# DC_buck_converter_3_3V_OP.net
KiCad netlist of a schematic drawn in Altium Designer
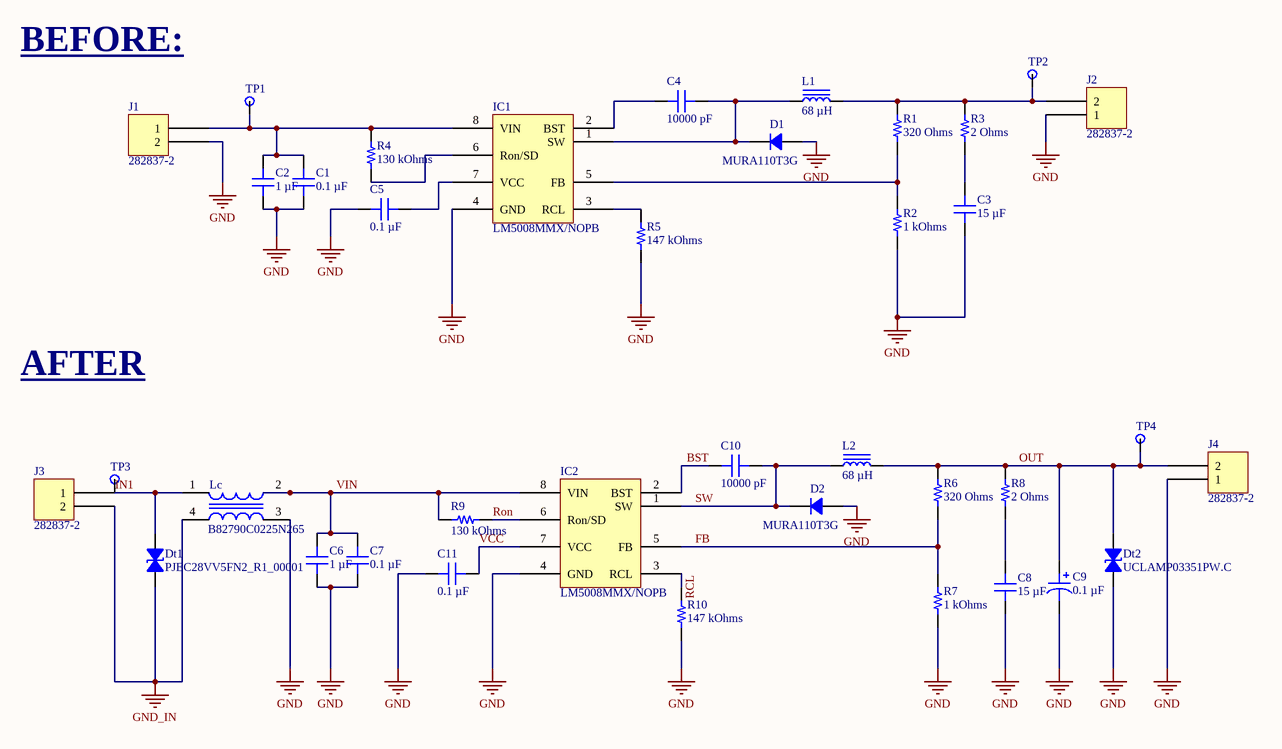
[diagram p0: DC_buck_converter_3.3V_OP..SchDoc]

(export (version "E")
  (design (tool "Eeschema 10.0.6"))
  (components
    (comp (ref "C1")
      (value "0.1 µF")
      (footprint "CAP 0603_1608")
      (description "CAP CER 0.1UF 50V X7R 0603")
      (fields (field (name "PART NUMBER") "C0603C104K5RAC7411") (field (name "MANUFACTURER") "KEMET"))
      (libsource (lib "Celestial Altium Library - altium_library") (part "Capacitor"))
    )
    (comp (ref "C2")
      (value "1 µF")
      (footprint "CAP 0603_1608")
      (description "CAP CER 1UF 50V X5R 0603")
      (fields (field (name "PART NUMBER") "UMK107ABJ105MAHT") (field (name "MANUFACTURER") "Taiyo Yuden"))
      (libsource (lib "Celestial Altium Library - altium_library") (part "Capacitor"))
    )
    (comp (ref "C3")
      (value "15 µF")
      (footprint "CAP 0603_1608")
      (description "CAP CER 15UF 6.3V X5R 0603")
      (fields
        (field (name "PART NUMBER") "C1608X5R0J156M080AC")
        (field (name "MANUFACTURER") "TDK Corporation")
      )
      (libsource (lib "Celestial Altium Library - altium_library") (part "Capacitor"))
    )
    (comp (ref "C4")
      (value "10000 pF")
      (footprint "CAP 0603_1608")
      (description "CAP CER 10000PF 100V X7R 0603")
      (fields (field (name "PART NUMBER") "AC0603KRX7R0BB103") (field (name "MANUFACTURER") "Yageo"))
      (libsource (lib "Celestial Altium Library - altium_library") (part "Capacitor"))
    )
    (comp (ref "C5")
      (value "0.1 µF")
      (footprint "CAP 0603_1608")
      (description "CAP CER 0.1UF 50V X7R 0603")
      (fields (field (name "PART NUMBER") "C0603C104K5RAC7411") (field (name "MANUFACTURER") "KEMET"))
      (libsource (lib "Celestial Altium Library - altium_library") (part "Capacitor"))
    )
    (comp (ref "C6")
      (value "1 µF")
      (footprint "CAP 0603_1608")
      (description "CAP CER 1UF 50V X5R 0603")
      (fields (field (name "PART NUMBER") "UMK107ABJ105MAHT") (field (name "MANUFACTURER") "Taiyo Yuden"))
      (libsource (lib "Celestial Altium Library - altium_library") (part "Capacitor"))
    )
    (comp (ref "C7")
      (value "0.1 µF")
      (footprint "CAP 0603_1608")
      (description "CAP CER 0.1UF 50V X7R 0603")
      (fields (field (name "PART NUMBER") "C0603C104K5RAC7411") (field (name "MANUFACTURER") "KEMET"))
      (libsource (lib "Celestial Altium Library - altium_library") (part "Capacitor"))
    )
    (comp (ref "C8")
      (value "15 µF")
      (footprint "CAP 0603_1608")
      (description "CAP CER 15UF 6.3V X5R 0603")
      (fields
        (field (name "PART NUMBER") "C1608X5R0J156M080AC")
        (field (name "MANUFACTURER") "TDK Corporation")
      )
      (libsource (lib "Celestial Altium Library - altium_library") (part "Capacitor"))
    )
    (comp (ref "C9")
      (value "0.1 µF")
      (footprint "CAP POL 1206_3216")
      (description "CAP TANT 0.1UF 10% 35V 1206")
      (fields (field (name "PART NUMBER") "T494A104K035AT") (field (name "MANUFACTURER") "KEMET"))
      (libsource (lib "Celestial Altium Library - altium_library") (part "Polarised Capacitor"))
    )
    (comp (ref "C10")
      (value "10000 pF")
      (footprint "CAP 0603_1608")
      (description "CAP CER 10000PF 100V X7R 0603")
      (fields (field (name "PART NUMBER") "AC0603KRX7R0BB103") (field (name "MANUFACTURER") "Yageo"))
      (libsource (lib "Celestial Altium Library - altium_library") (part "Capacitor"))
    )
    (comp (ref "C11")
      (value "0.1 µF")
      (footprint "CAP 0603_1608")
      (description "CAP CER 0.1UF 50V X7R 0603")
      (fields (field (name "PART NUMBER") "C0603C104K5RAC7411") (field (name "MANUFACTURER") "KEMET"))
      (libsource (lib "Celestial Altium Library - altium_library") (part "Capacitor"))
    )
    (comp (ref "D1")
      (value "MURA110T3G")
      (footprint "DO214AC SMA")
      (description "DIODE GEN PURP 100V 2A SMA")
      (fields (field (name "MANUFACTURER") "ON Semiconductor"))
      (libsource (lib "Celestial Altium Library - altium_library") (part "Diode"))
    )
    (comp (ref "D2")
      (value "MURA110T3G")
      (footprint "DO214AC SMA")
      (description "DIODE GEN PURP 100V 2A SMA")
      (fields (field (name "MANUFACTURER") "ON Semiconductor"))
      (libsource (lib "Celestial Altium Library - altium_library") (part "Diode"))
    )
    (comp (ref "Dt1")
      (value "PJEC28VV5FN2_R1_00001")
      (footprint "0402")
      (description "ESD PROTECTION")
      (fields (field (name "MANUFACTURER") "Panjit International Inc."))
      (libsource (lib "Celestial Altium Library - altium_library") (part "Diode TVS"))
    )
    (comp (ref "Dt2")
      (value "UCLAMP03351PW.C")
      (footprint "0402")
      (description "3,3V ESD & EOS PROTECTION")
      (fields (field (name "MANUFACTURER") "Semtech Corporation"))
      (libsource (lib "Celestial Altium Library - altium_library") (part "Diode TVS"))
    )
    (comp (ref "IC1")
      (value "LM5008MMX/NOPB")
      (footprint "TI VSSOP-8 DGK")
      (description "IC REG BUCK ADJ 350MA 8VSSOP")
      (fields (field (name "MANUFACTURER") "Texas Instruments"))
      (libsource (lib "Celestial Altium Library - altium_library") (part "TI LM5008"))
    )
    (comp (ref "IC2")
      (value "LM5008MMX/NOPB")
      (footprint "TI VSSOP-8 DGK")
      (description "IC REG BUCK ADJ 350MA 8VSSOP")
      (fields (field (name "MANUFACTURER") "Texas Instruments"))
      (libsource (lib "Celestial Altium Library - altium_library") (part "TI LM5008"))
    )
    (comp (ref "J1")
      (value "282837-2")
      (footprint "TE 282837-2")
      (description "TERM BLK 2P SIDE ENT 5.08MM PCB")
      (fields (field (name "MANUFACTURER") "TE Connectivity AMP Connectors") (field (name "VOLTAGE") "300 V"))
      (libsource (lib "") (part "2 Pin_1"))
    )
    (comp (ref "J2")
      (value "282837-2")
      (footprint "TE 282837-2")
      (description "TERM BLK 2P SIDE ENT 5.08MM PCB")
      (fields (field (name "MANUFACTURER") "TE Connectivity AMP Connectors") (field (name "VOLTAGE") "300 V"))
      (libsource (lib "Celestial Altium Library - altium_library") (part "2 Pin"))
    )
    (comp (ref "J3")
      (value "282837-2")
      (footprint "TE 282837-2")
      (description "TERM BLK 2P SIDE ENT 5.08MM PCB")
      (fields (field (name "MANUFACTURER") "TE Connectivity AMP Connectors") (field (name "VOLTAGE") "300 V"))
      (libsource (lib "") (part "2 Pin_1"))
    )
    (comp (ref "J4")
      (value "282837-2")
      (footprint "TE 282837-2")
      (description "TERM BLK 2P SIDE ENT 5.08MM PCB")
      (fields (field (name "MANUFACTURER") "TE Connectivity AMP Connectors") (field (name "VOLTAGE") "300 V"))
      (libsource (lib "Celestial Altium Library - altium_library") (part "2 Pin"))
    )
    (comp (ref "L1")
      (value "68 µH")
      (footprint "BOURNS SRR1280")
      (description "FIXED IND 68UH 2.4A 120 MOHM SMD")
      (fields (field (name "PART NUMBER") "SRR1280-680M") (field (name "MANUFACTURER") "Bourns Inc."))
      (libsource (lib "Celestial Altium Library - altium_library") (part "Inductor"))
    )
    (comp (ref "L2")
      (value "68 µH")
      (footprint "TDK SLF10145")
      (description "FIXED IND 68UH 1.3A 168 MOHM SMD")
      (fields
        (field (name "PART NUMBER") "SLF10145T-680M1R2-PF")
        (field (name "MANUFACTURER") "TDK Corporation")
      )
      (libsource (lib "Celestial Altium Library - altium_library") (part "Inductor"))
    )
    (comp (ref "Lc")
      (value "B82790C0225N265")
      (footprint "FL_B82790C0225N265")
      (description "Common Mode Filter / Choke, 0.005 - 4.7 mH, 200 - 1000 mA")
      (fields (field (name "MF") "EPCOS"))
      (libsource (lib "B82790C0225N265") (part "B82790C0225N265"))
    )
    (comp (ref "R1")
      (value "320 Ohms")
      (footprint "RES 0603_1608")
      (description "RES 320 OHM 0.5% 1/10W 0603")
      (fields (field (name "PART NUMBER") "RT0603DRE07320RL") (field (name "MANUFACTURER") "Yageo"))
      (libsource (lib "Celestial Altium Library - altium_library") (part "Resistor"))
    )
    (comp (ref "R2")
      (value "1 kOhms")
      (footprint "RES 0603_1608")
      (description "RES SMD 1K OHM 0.5% 1/10W 0603")
      (fields (field (name "PART NUMBER") "AT0603DRD071KL") (field (name "MANUFACTURER") "Yageo"))
      (libsource (lib "Celestial Altium Library - altium_library") (part "Resistor"))
    )
    (comp (ref "R3")
      (value "2 Ohms")
      (footprint "RES 0603_1608")
      (description "SULFUR TOLERANT CHIP RESISTORS")
      (fields (field (name "PART NUMBER") "SFR03EZPJ2R0") (field (name "MANUFACTURER") "Rohm Semiconductor"))
      (libsource (lib "Celestial Altium Library - altium_library") (part "Resistor"))
    )
    (comp (ref "R4")
      (value "130 kOhms")
      (footprint "RES 0603_1608")
      (description "RES SMD 130K OHM 1% 1/10W 0603")
      (fields (field (name "PART NUMBER") "CRCW0603130KFKEA") (field (name "MANUFACTURER") "Vishay Dale"))
      (libsource (lib "Celestial Altium Library - altium_library") (part "Resistor"))
    )
    (comp (ref "R5")
      (value "147 kOhms")
      (footprint "RES 0603_1608")
      (description "RES SMD 147K OHM 0.1% 1/10W 0603")
      (fields (field (name "PART NUMBER") "RT0603BRD07147KL") (field (name "MANUFACTURER") "Yageo"))
      (libsource (lib "Celestial Altium Library - altium_library") (part "Resistor"))
    )
    (comp (ref "R6")
      (value "320 Ohms")
      (footprint "RES 0603_1608")
      (description "RES 320 OHM 0.5% 1/10W 0603")
      (fields (field (name "PART NUMBER") "RT0603DRE07320RL") (field (name "MANUFACTURER") "Yageo"))
      (libsource (lib "Celestial Altium Library - altium_library") (part "Resistor"))
    )
    (comp (ref "R7")
      (value "1 kOhms")
      (footprint "RES 0603_1608")
      (description "RES SMD 1K OHM 0.5% 1/10W 0603")
      (fields (field (name "PART NUMBER") "AT0603DRD071KL") (field (name "MANUFACTURER") "Yageo"))
      (libsource (lib "Celestial Altium Library - altium_library") (part "Resistor"))
    )
    (comp (ref "R8")
      (value "2 Ohms")
      (footprint "RES 0603_1608")
      (description "SULFUR TOLERANT CHIP RESISTORS")
      (fields (field (name "PART NUMBER") "SFR03EZPJ2R0") (field (name "MANUFACTURER") "Rohm Semiconductor"))
      (libsource (lib "Celestial Altium Library - altium_library") (part "Resistor"))
    )
    (comp (ref "R9")
      (value "130 kOhms")
      (footprint "RES 0603_1608")
      (description "RES SMD 130K OHM 1% 1/10W 0603")
      (fields (field (name "PART NUMBER") "CRCW0603130KFKEA") (field (name "MANUFACTURER") "Vishay Dale"))
      (libsource (lib "Celestial Altium Library - altium_library") (part "Resistor"))
    )
    (comp (ref "R10")
      (value "147 kOhms")
      (footprint "RES 0603_1608")
      (description "RES SMD 147K OHM 0.1% 1/10W 0603")
      (fields (field (name "PART NUMBER") "RT0603BRD07147KL") (field (name "MANUFACTURER") "Yageo"))
      (libsource (lib "Celestial Altium Library - altium_library") (part "Resistor"))
    )
    (comp (ref "TP1") (value "TP_1") (footprint "Testpoint") (libsource (lib "Schlib1") (part "Testpoint")))
    (comp (ref "TP2") (value "TP_1") (footprint "Testpoint") (libsource (lib "Schlib1") (part "Testpoint")))
    (comp (ref "TP3") (value "TP_1") (footprint "Testpoint") (libsource (lib "Schlib1") (part "Testpoint")))
    (comp (ref "TP4") (value "TP_1") (footprint "Testpoint") (libsource (lib "Schlib1") (part "Testpoint")))
  )
  (nets
    (net (code "1") (name "/BST") (class "Default")
      (node (ref "C10") (pin "1") (pinfunction "1_1") (pintype "passive"))
      (node (ref "IC2") (pin "2") (pinfunction "BST_2") (pintype "passive"))
    )
    (net (code "2") (name "/FB") (class "Default")
      (node (ref "IC2") (pin "5") (pinfunction "FB_5") (pintype "passive"))
      (node (ref "R6") (pin "1") (pinfunction "1_1") (pintype "passive"))
      (node (ref "R7") (pin "2") (pinfunction "2_2") (pintype "passive"))
    )
    (net (code "3") (name "/IN1") (class "Default")
      (node (ref "Dt1") (pin "2") (pinfunction "2_2") (pintype "passive"))
      (node (ref "J3") (pin "1") (pinfunction "1_1") (pintype "passive"))
      (node (ref "Lc") (pin "1") (pinfunction "1_1") (pintype "passive"))
    )
    (net (code "4") (name "/OUT") (class "Default")
      (node (ref "C9") (pin "1") (pinfunction "1_1") (pintype "passive"))
      (node (ref "Dt2") (pin "2") (pinfunction "2_2") (pintype "passive"))
      (node (ref "J4") (pin "2") (pinfunction "2_2") (pintype "passive"))
      (node (ref "L2") (pin "2") (pinfunction "2_2") (pintype "passive"))
      (node (ref "R6") (pin "2") (pinfunction "2_2") (pintype "passive"))
      (node (ref "R8") (pin "2") (pinfunction "2_2") (pintype "passive"))
    )
    (net (code "5") (name "/RCL") (class "Default")
      (node (ref "IC2") (pin "3") (pinfunction "RCL_3") (pintype "passive"))
      (node (ref "R10") (pin "1") (pinfunction "1_1") (pintype "passive"))
    )
    (net (code "6") (name "/Ron") (class "Default")
      (node (ref "IC2") (pin "6") (pinfunction "Ron/SD_6") (pintype "passive"))
      (node (ref "R9") (pin "2") (pinfunction "2_2") (pintype "passive"))
    )
    (net (code "7") (name "/SW") (class "Default")
      (node (ref "C10") (pin "2") (pinfunction "2_2") (pintype "passive"))
      (node (ref "D2") (pin "2") (pinfunction "2_2") (pintype "passive"))
      (node (ref "IC2") (pin "1") (pinfunction "SW_1") (pintype "passive"))
      (node (ref "L2") (pin "1") (pinfunction "1_1") (pintype "passive"))
    )
    (net (code "8") (name "/VCC") (class "Default")
      (node (ref "C11") (pin "1") (pinfunction "1_1") (pintype "passive"))
      (node (ref "IC2") (pin "7") (pinfunction "VCC_7") (pintype "passive"))
    )
    (net (code "9") (name "/VIN") (class "Default")
      (node (ref "C6") (pin "2") (pinfunction "2_2") (pintype "passive"))
      (node (ref "C7") (pin "2") (pinfunction "2_2") (pintype "passive"))
      (node (ref "IC2") (pin "8") (pinfunction "VIN_8") (pintype "passive"))
      (node (ref "Lc") (pin "2") (pinfunction "2_2") (pintype "passive"))
      (node (ref "R9") (pin "1") (pinfunction "1_1") (pintype "passive"))
    )
    (net (code "10") (name "GND") (class "Default")
      (node (ref "C1") (pin "1") (pinfunction "1_1") (pintype "passive"))
      (node (ref "C11") (pin "2") (pinfunction "2_2") (pintype "passive"))
      (node (ref "C2") (pin "1") (pinfunction "1_1") (pintype "passive"))
      (node (ref "C3") (pin "1") (pinfunction "1_1") (pintype "passive"))
      (node (ref "C5") (pin "2") (pinfunction "2_2") (pintype "passive"))
      (node (ref "C6") (pin "1") (pinfunction "1_1") (pintype "passive"))
      (node (ref "C7") (pin "1") (pinfunction "1_1") (pintype "passive"))
      (node (ref "C8") (pin "1") (pinfunction "1_1") (pintype "passive"))
      (node (ref "C9") (pin "2") (pinfunction "2_2") (pintype "passive"))
      (node (ref "D1") (pin "1") (pinfunction "1_1") (pintype "passive"))
      (node (ref "D2") (pin "1") (pinfunction "1_1") (pintype "passive"))
      (node (ref "Dt2") (pin "1") (pinfunction "1_1") (pintype "passive"))
      (node (ref "IC1") (pin "4") (pinfunction "GND_4") (pintype "passive"))
      (node (ref "IC2") (pin "4") (pinfunction "GND_4") (pintype "passive"))
      (node (ref "J1") (pin "2") (pinfunction "2_2") (pintype "passive"))
      (node (ref "J2") (pin "1") (pinfunction "1_1") (pintype "passive"))
      (node (ref "J4") (pin "1") (pinfunction "1_1") (pintype "passive"))
      (node (ref "Lc") (pin "3") (pinfunction "3_3") (pintype "passive"))
      (node (ref "R10") (pin "2") (pinfunction "2_2") (pintype "passive"))
      (node (ref "R2") (pin "1") (pinfunction "1_1") (pintype "passive"))
      (node (ref "R5") (pin "2") (pinfunction "2_2") (pintype "passive"))
      (node (ref "R7") (pin "1") (pinfunction "1_1") (pintype "passive"))
    )
    (net (code "11") (name "GND_IN") (class "Default")
      (node (ref "Dt1") (pin "1") (pinfunction "1_1") (pintype "passive"))
      (node (ref "J3") (pin "2") (pinfunction "2_2") (pintype "passive"))
      (node (ref "Lc") (pin "4") (pinfunction "4_4") (pintype "passive"))
    )
    (net (code "12") (name "Net-(C3-Pad2)") (class "Default")
      (node (ref "C3") (pin "2") (pinfunction "2_2") (pintype "passive"))
      (node (ref "R3") (pin "1") (pinfunction "1_1") (pintype "passive"))
    )
    (net (code "13") (name "Net-(C8-Pad2)") (class "Default")
      (node (ref "C8") (pin "2") (pinfunction "2_2") (pintype "passive"))
      (node (ref "R8") (pin "1") (pinfunction "1_1") (pintype "passive"))
    )
    (net (code "14") (name "Net-(IC1-BST)") (class "Default")
      (node (ref "C4") (pin "1") (pinfunction "1_1") (pintype "passive"))
      (node (ref "IC1") (pin "2") (pinfunction "BST_2") (pintype "passive"))
    )
    (net (code "15") (name "Net-(IC1-FB)") (class "Default")
      (node (ref "IC1") (pin "5") (pinfunction "FB_5") (pintype "passive"))
      (node (ref "R1") (pin "1") (pinfunction "1_1") (pintype "passive"))
      (node (ref "R2") (pin "2") (pinfunction "2_2") (pintype "passive"))
    )
    (net (code "16") (name "Net-(IC1-RCL)") (class "Default")
      (node (ref "IC1") (pin "3") (pinfunction "RCL_3") (pintype "passive"))
      (node (ref "R5") (pin "1") (pinfunction "1_1") (pintype "passive"))
    )
    (net (code "17") (name "Net-(IC1-Ron{slash}SD)") (class "Default")
      (node (ref "IC1") (pin "6") (pinfunction "Ron/SD_6") (pintype "passive"))
      (node (ref "R4") (pin "2") (pinfunction "2_2") (pintype "passive"))
    )
    (net (code "18") (name "Net-(IC1-SW)") (class "Default")
      (node (ref "C4") (pin "2") (pinfunction "2_2") (pintype "passive"))
      (node (ref "D1") (pin "2") (pinfunction "2_2") (pintype "passive"))
      (node (ref "IC1") (pin "1") (pinfunction "SW_1") (pintype "passive"))
      (node (ref "L1") (pin "1") (pinfunction "1_1") (pintype "passive"))
    )
    (net (code "19") (name "Net-(IC1-VCC)") (class "Default")
      (node (ref "C5") (pin "1") (pinfunction "1_1") (pintype "passive"))
      (node (ref "IC1") (pin "7") (pinfunction "VCC_7") (pintype "passive"))
    )
    (net (code "20") (name "Net-(IC1-VIN)") (class "Default")
      (node (ref "C1") (pin "2") (pinfunction "2_2") (pintype "passive"))
      (node (ref "C2") (pin "2") (pinfunction "2_2") (pintype "passive"))
      (node (ref "IC1") (pin "8") (pinfunction "VIN_8") (pintype "passive"))
      (node (ref "J1") (pin "1") (pinfunction "1_1") (pintype "passive"))
      (node (ref "R4") (pin "1") (pinfunction "1_1") (pintype "passive"))
    )
    (net (code "21") (name "Net-(J2-Pad2)") (class "Default")
      (node (ref "J2") (pin "2") (pinfunction "2_2") (pintype "passive"))
      (node (ref "L1") (pin "2") (pinfunction "2_2") (pintype "passive"))
      (node (ref "R1") (pin "2") (pinfunction "2_2") (pintype "passive"))
      (node (ref "R3") (pin "2") (pinfunction "2_2") (pintype "passive"))
    )
  )
)
